# Pumpkin.net
KiCad netlist of a schematic drawn in EAGLE
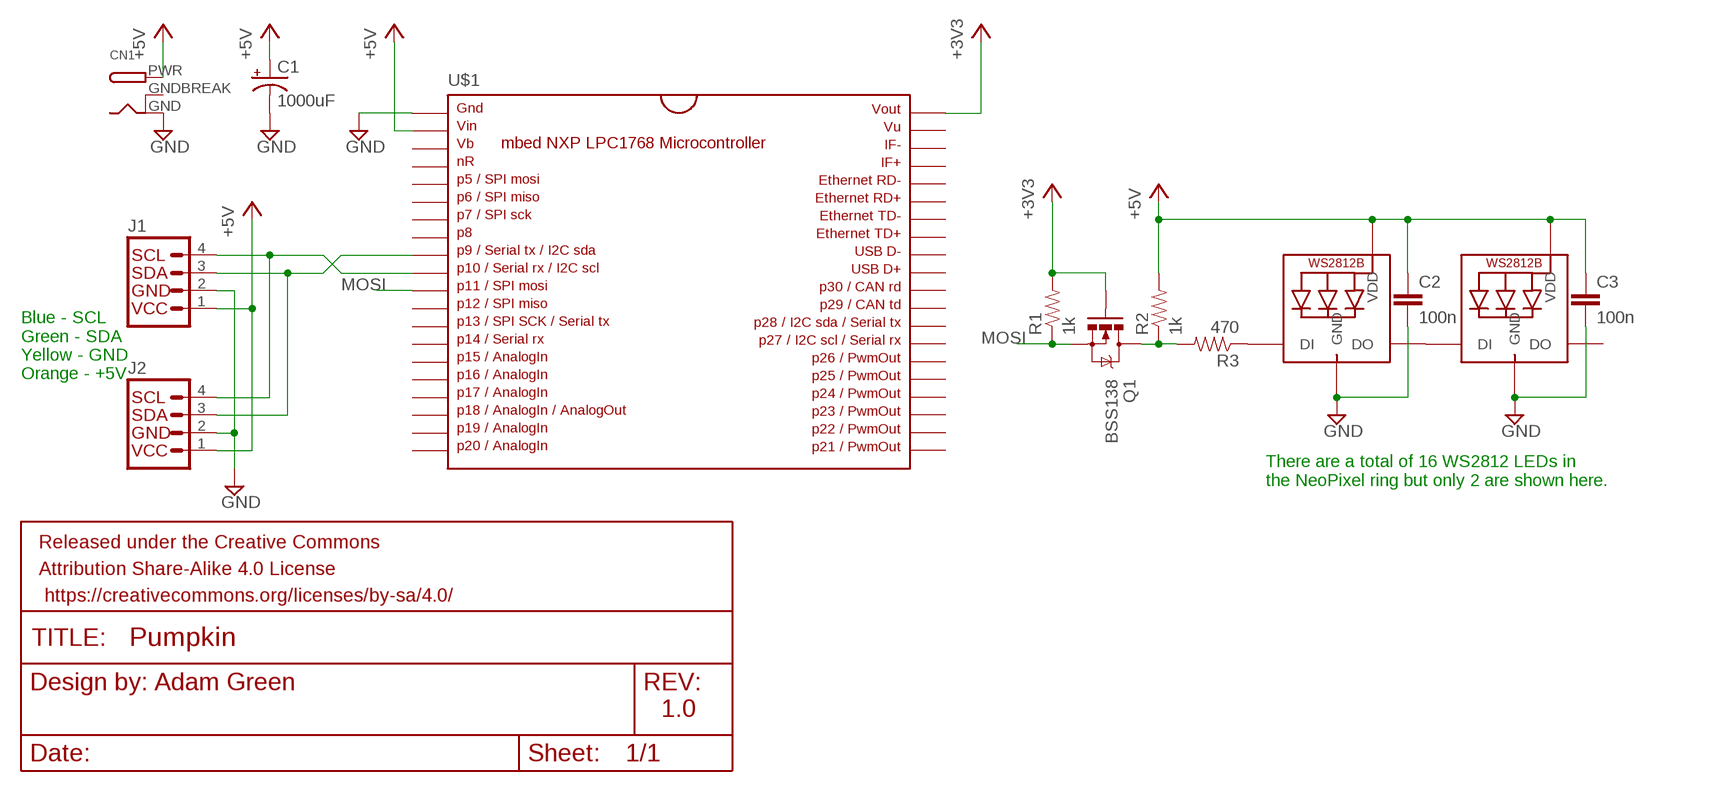
[diagram p0: schematic, sheet 1]

(export (version "E")
  (design (tool "Eeschema 10.0.6"))
  (components
    (comp (ref "C1")
      (value "1000uF")
      (footprint "eagle-import:CPOL-RADIAL-1000UF-25V")
      (libsource (lib "eagle-import") (part "CAP_POLPTH4"))
    )
    (comp (ref "C2")
      (value "100n")
      (footprint "eagle-import:0805")
      (libsource (lib "eagle-import") (part "CAP0805"))
    )
    (comp (ref "C3")
      (value "100n")
      (footprint "eagle-import:0805")
      (libsource (lib "eagle-import") (part "CAP0805"))
    )
    (comp (ref "CN1")
      (value "DCBARRELPTH")
      (footprint "eagle-import:DCJACK_2MM_PTH")
      (libsource (lib "eagle-import") (part "DCBARRELPTH"))
    )
    (comp (ref "J1")
      (value "I2C_LEDEYES")
      (footprint "eagle-import:1X04")
      (libsource (lib "eagle-import") (part "I2C_LEDEYES"))
    )
    (comp (ref "J2")
      (value "I2C_LEDEYES")
      (footprint "eagle-import:1X04")
      (libsource (lib "eagle-import") (part "I2C_LEDEYES"))
    )
    (comp (ref "LED1")
      (value "WS2812B3535")
      (footprint "eagle-import:LED3535")
      (libsource (lib "eagle-import") (part "WS2812B3535"))
    )
    (comp (ref "LED2")
      (value "WS2812B3535")
      (footprint "eagle-import:LED3535")
      (libsource (lib "eagle-import") (part "WS2812B3535"))
    )
    (comp (ref "Q1")
      (value "BSS138")
      (footprint "eagle-import:SOT23-3")
      (libsource (lib "eagle-import") (part "MOSFET-NCHANNELBSS138"))
    )
    (comp (ref "R1")
      (value "1k")
      (footprint "eagle-import:0805")
      (libsource (lib "eagle-import") (part "RESISTOR0805-RES"))
    )
    (comp (ref "R2")
      (value "1k")
      (footprint "eagle-import:0805")
      (libsource (lib "eagle-import") (part "RESISTOR0805-RES"))
    )
    (comp (ref "R3")
      (value "470")
      (footprint "eagle-import:0805")
      (libsource (lib "eagle-import") (part "RESISTOR0805-RES"))
    )
    (comp (ref "U$1")
      (value "MBED_NXP_LPC1768")
      (footprint "eagle-import:DIL40_0.9")
      (libsource (lib "eagle-import") (part "MBED_NXP_LPC1768"))
    )
  )
  (nets
    (net (code "1") (name "+3V3") (class "Default")
      (node (ref "Q1") (pin "1") (pinfunction "G_1") (pintype "passive"))
      (node (ref "R1") (pin "2") (pinfunction "2_2") (pintype "passive"))
      (node (ref "U$1") (pin "40") (pinfunction "P$40_40") (pintype "bidirectional"))
    )
    (net (code "2") (name "+5V") (class "Default")
      (node (ref "C1") (pin "1") (pinfunction "+_1") (pintype "passive"))
      (node (ref "C2") (pin "1") (pinfunction "1_1") (pintype "passive"))
      (node (ref "C3") (pin "1") (pinfunction "1_1") (pintype "passive"))
      (node (ref "CN1") (pin "PWR") (pinfunction "PWR_PWR") (pintype "power_in"))
      (node (ref "J1") (pin "1") (pinfunction "1_1") (pintype "passive"))
      (node (ref "J2") (pin "1") (pinfunction "1_1") (pintype "passive"))
      (node (ref "LED1") (pin "2") (pinfunction "VDD_2") (pintype "power_in"))
      (node (ref "LED2") (pin "2") (pinfunction "VDD_2") (pintype "power_in"))
      (node (ref "R2") (pin "2") (pinfunction "2_2") (pintype "passive"))
      (node (ref "U$1") (pin "2") (pinfunction "P$2_2") (pintype "bidirectional"))
    )
    (net (code "3") (name "/GNDBREAK") (class "Default")
      (node (ref "CN1") (pin "GNDBREAK") (pinfunction "GNDBREAK_GNDBREAK") (pintype "power_in"))
    )
    (net (code "4") (name "/MOSI") (class "Default")
      (node (ref "Q1") (pin "2") (pinfunction "S_2") (pintype "passive"))
      (node (ref "R1") (pin "1") (pinfunction "1_1") (pintype "passive"))
      (node (ref "U$1") (pin "11") (pinfunction "P$11_11") (pintype "bidirectional"))
    )
    (net (code "5") (name "GND") (class "Default")
      (node (ref "C1") (pin "2") (pinfunction "-_2") (pintype "passive"))
      (node (ref "C2") (pin "2") (pinfunction "2_2") (pintype "passive"))
      (node (ref "C3") (pin "2") (pinfunction "2_2") (pintype "passive"))
      (node (ref "CN1") (pin "GND") (pinfunction "GND_GND") (pintype "power_in"))
      (node (ref "J1") (pin "2") (pinfunction "2_2") (pintype "passive"))
      (node (ref "J2") (pin "2") (pinfunction "2_2") (pintype "passive"))
      (node (ref "LED1") (pin "4") (pinfunction "GND_4") (pintype "power_in"))
      (node (ref "LED2") (pin "4") (pinfunction "GND_4") (pintype "power_in"))
      (node (ref "U$1") (pin "1") (pinfunction "P$1_1") (pintype "bidirectional"))
    )
    (net (code "6") (name "Net-(LED1-DI)") (class "Default")
      (node (ref "LED1") (pin "1") (pinfunction "DI_1") (pintype "input"))
      (node (ref "R3") (pin "1") (pinfunction "1_1") (pintype "passive"))
    )
    (net (code "7") (name "Net-(LED1-DO)") (class "Default")
      (node (ref "LED1") (pin "3") (pinfunction "DO_3") (pintype "output"))
      (node (ref "LED2") (pin "1") (pinfunction "DI_1") (pintype "input"))
    )
    (net (code "8") (name "Net-(Q1-D)") (class "Default")
      (node (ref "Q1") (pin "3") (pinfunction "D_3") (pintype "passive"))
      (node (ref "R2") (pin "1") (pinfunction "1_1") (pintype "passive"))
      (node (ref "R3") (pin "2") (pinfunction "2_2") (pintype "passive"))
    )
    (net (code "9") (name "Net-(U$1-P$9)") (class "Default")
      (node (ref "J1") (pin "3") (pinfunction "3_3") (pintype "passive"))
      (node (ref "J2") (pin "3") (pinfunction "3_3") (pintype "passive"))
      (node (ref "U$1") (pin "9") (pinfunction "P$9_9") (pintype "bidirectional"))
    )
    (net (code "10") (name "Net-(U$1-P$10)") (class "Default")
      (node (ref "J1") (pin "4") (pinfunction "4_4") (pintype "passive"))
      (node (ref "J2") (pin "4") (pinfunction "4_4") (pintype "passive"))
      (node (ref "U$1") (pin "10") (pinfunction "P$10_10") (pintype "bidirectional"))
    )
    (net (code "11") (name "unconnected-(LED2-DO-Pad3)") (class "Default")
      (node (ref "LED2") (pin "3") (pinfunction "DO_3") (pintype "output"))
    )
    (net (code "12") (name "unconnected-(U$1-P$3-Pad3)") (class "Default")
      (node (ref "U$1") (pin "3") (pinfunction "P$3_3") (pintype "bidirectional"))
    )
    (net (code "13") (name "unconnected-(U$1-P$4-Pad4)") (class "Default")
      (node (ref "U$1") (pin "4") (pinfunction "P$4_4") (pintype "bidirectional"))
    )
    (net (code "14") (name "unconnected-(U$1-P$5-Pad5)") (class "Default")
      (node (ref "U$1") (pin "5") (pinfunction "P$5_5") (pintype "bidirectional"))
    )
    (net (code "15") (name "unconnected-(U$1-P$6-Pad6)") (class "Default")
      (node (ref "U$1") (pin "6") (pinfunction "P$6_6") (pintype "bidirectional"))
    )
    (net (code "16") (name "unconnected-(U$1-P$7-Pad7)") (class "Default")
      (node (ref "U$1") (pin "7") (pinfunction "P$7_7") (pintype "bidirectional"))
    )
    (net (code "17") (name "unconnected-(U$1-P$8-Pad8)") (class "Default")
      (node (ref "U$1") (pin "8") (pinfunction "P$8_8") (pintype "bidirectional"))
    )
    (net (code "18") (name "unconnected-(U$1-P$12-Pad12)") (class "Default")
      (node (ref "U$1") (pin "12") (pinfunction "P$12_12") (pintype "bidirectional"))
    )
    (net (code "19") (name "unconnected-(U$1-P$13-Pad13)") (class "Default")
      (node (ref "U$1") (pin "13") (pinfunction "P$13_13") (pintype "bidirectional"))
    )
    (net (code "20") (name "unconnected-(U$1-P$14-Pad14)") (class "Default")
      (node (ref "U$1") (pin "14") (pinfunction "P$14_14") (pintype "bidirectional"))
    )
    (net (code "21") (name "unconnected-(U$1-P$15-Pad15)") (class "Default")
      (node (ref "U$1") (pin "15") (pinfunction "P$15_15") (pintype "bidirectional"))
    )
    (net (code "22") (name "unconnected-(U$1-P$16-Pad16)") (class "Default")
      (node (ref "U$1") (pin "16") (pinfunction "P$16_16") (pintype "bidirectional"))
    )
    (net (code "23") (name "unconnected-(U$1-P$17-Pad17)") (class "Default")
      (node (ref "U$1") (pin "17") (pinfunction "P$17_17") (pintype "bidirectional"))
    )
    (net (code "24") (name "unconnected-(U$1-P$18-Pad18)") (class "Default")
      (node (ref "U$1") (pin "18") (pinfunction "P$18_18") (pintype "bidirectional"))
    )
    (net (code "25") (name "unconnected-(U$1-P$19-Pad19)") (class "Default")
      (node (ref "U$1") (pin "19") (pinfunction "P$19_19") (pintype "bidirectional"))
    )
    (net (code "26") (name "unconnected-(U$1-P$20-Pad20)") (class "Default")
      (node (ref "U$1") (pin "20") (pinfunction "P$20_20") (pintype "bidirectional"))
    )
    (net (code "27") (name "unconnected-(U$1-P$21-Pad21)") (class "Default")
      (node (ref "U$1") (pin "21") (pinfunction "P$21_21") (pintype "bidirectional"))
    )
    (net (code "28") (name "unconnected-(U$1-P$22-Pad22)") (class "Default")
      (node (ref "U$1") (pin "22") (pinfunction "P$22_22") (pintype "bidirectional"))
    )
    (net (code "29") (name "unconnected-(U$1-P$23-Pad23)") (class "Default")
      (node (ref "U$1") (pin "23") (pinfunction "P$23_23") (pintype "bidirectional"))
    )
    (net (code "30") (name "unconnected-(U$1-P$24-Pad24)") (class "Default")
      (node (ref "U$1") (pin "24") (pinfunction "P$24_24") (pintype "bidirectional"))
    )
    (net (code "31") (name "unconnected-(U$1-P$25-Pad25)") (class "Default")
      (node (ref "U$1") (pin "25") (pinfunction "P$25_25") (pintype "bidirectional"))
    )
    (net (code "32") (name "unconnected-(U$1-P$26-Pad26)") (class "Default")
      (node (ref "U$1") (pin "26") (pinfunction "P$26_26") (pintype "bidirectional"))
    )
    (net (code "33") (name "unconnected-(U$1-P$27-Pad27)") (class "Default")
      (node (ref "U$1") (pin "27") (pinfunction "P$27_27") (pintype "bidirectional"))
    )
    (net (code "34") (name "unconnected-(U$1-P$28-Pad28)") (class "Default")
      (node (ref "U$1") (pin "28") (pinfunction "P$28_28") (pintype "bidirectional"))
    )
    (net (code "35") (name "unconnected-(U$1-P$29-Pad29)") (class "Default")
      (node (ref "U$1") (pin "29") (pinfunction "P$29_29") (pintype "bidirectional"))
    )
    (net (code "36") (name "unconnected-(U$1-P$30-Pad30)") (class "Default")
      (node (ref "U$1") (pin "30") (pinfunction "P$30_30") (pintype "bidirectional"))
    )
    (net (code "37") (name "unconnected-(U$1-P$31-Pad31)") (class "Default")
      (node (ref "U$1") (pin "31") (pinfunction "P$31_31") (pintype "bidirectional"))
    )
    (net (code "38") (name "unconnected-(U$1-P$32-Pad32)") (class "Default")
      (node (ref "U$1") (pin "32") (pinfunction "P$32_32") (pintype "bidirectional"))
    )
    (net (code "39") (name "unconnected-(U$1-P$33-Pad33)") (class "Default")
      (node (ref "U$1") (pin "33") (pinfunction "P$33_33") (pintype "bidirectional"))
    )
    (net (code "40") (name "unconnected-(U$1-P$34-Pad34)") (class "Default")
      (node (ref "U$1") (pin "34") (pinfunction "P$34_34") (pintype "bidirectional"))
    )
    (net (code "41") (name "unconnected-(U$1-P$35-Pad35)") (class "Default")
      (node (ref "U$1") (pin "35") (pinfunction "P$35_35") (pintype "bidirectional"))
    )
    (net (code "42") (name "unconnected-(U$1-P$36-Pad36)") (class "Default")
      (node (ref "U$1") (pin "36") (pinfunction "P$36_36") (pintype "bidirectional"))
    )
    (net (code "43") (name "unconnected-(U$1-P$37-Pad37)") (class "Default")
      (node (ref "U$1") (pin "37") (pinfunction "P$37_37") (pintype "bidirectional"))
    )
    (net (code "44") (name "unconnected-(U$1-P$38-Pad38)") (class "Default")
      (node (ref "U$1") (pin "38") (pinfunction "P$38_38") (pintype "bidirectional"))
    )
    (net (code "45") (name "unconnected-(U$1-P$39-Pad39)") (class "Default")
      (node (ref "U$1") (pin "39") (pinfunction "P$39_39") (pintype "bidirectional"))
    )
  )
)
